# rfid.net
KiCad netlist of a schematic drawn in EAGLE
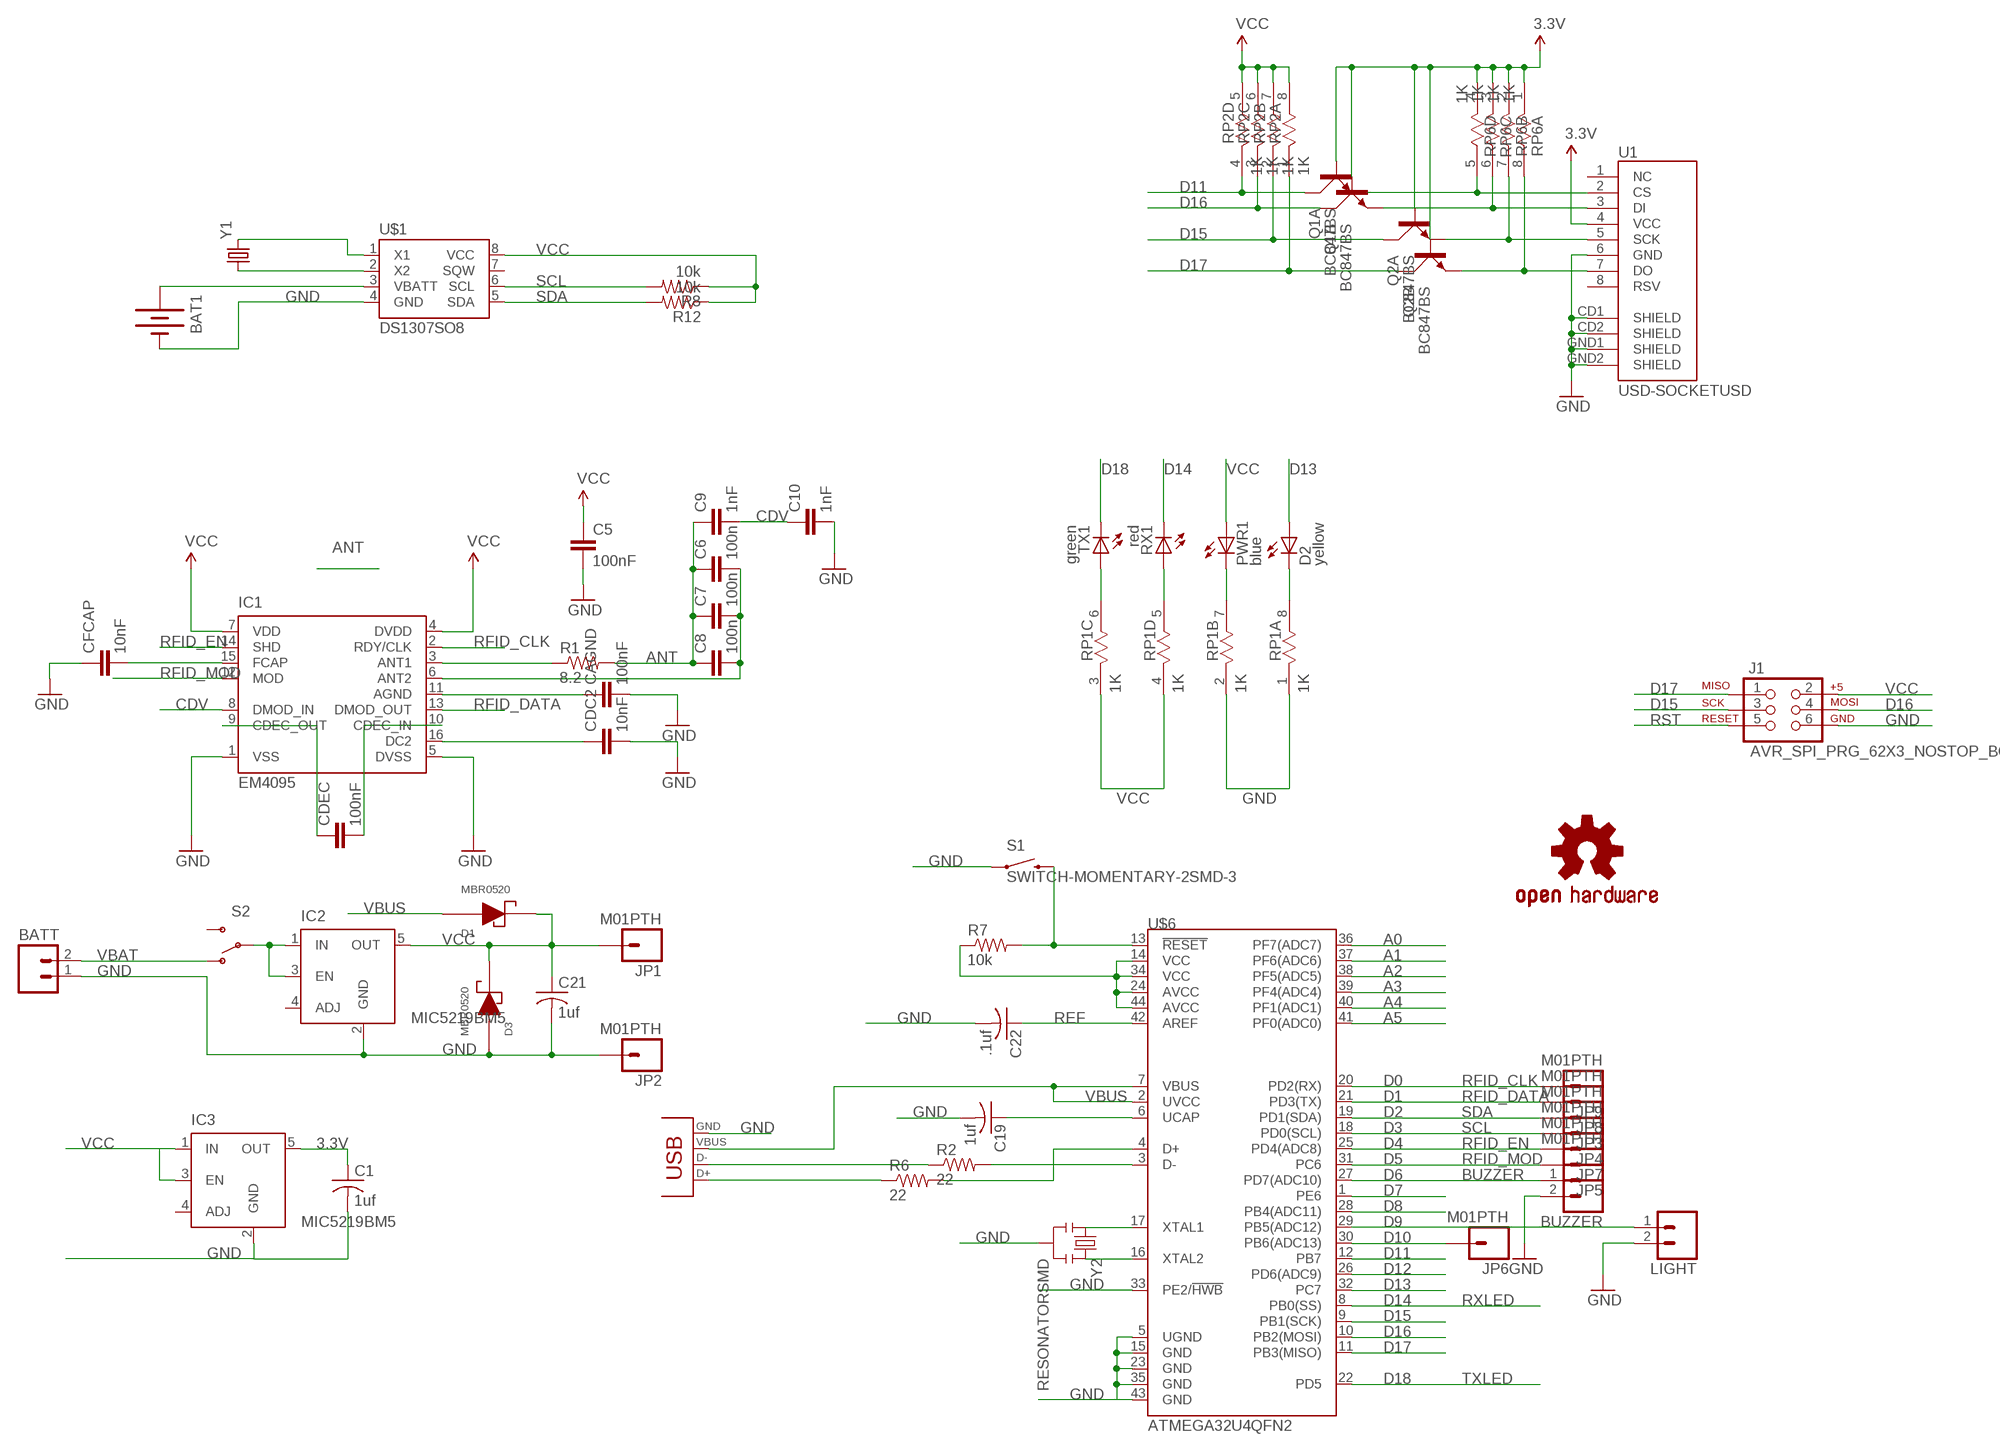
[diagram p0: schematic, sheet 1]

(export (version "E")
  (design (tool "Eeschema 10.0.6"))
  (components
    (comp (ref "BAT1")
      (value "BATTERY12MM")
      (footprint "eagle-import:BATTCON_12MM")
      (libsource (lib "eagle-import") (part "BATTERY12MM"))
    )
    (comp (ref "BATT")
      (value "M02PTH")
      (footprint "eagle-import:1X02")
      (libsource (lib "eagle-import") (part "M02PTH"))
    )
    (comp (ref "BUZZER")
      (value "M02PTH")
      (footprint "eagle-import:1X02")
      (libsource (lib "eagle-import") (part "M02PTH"))
    )
    (comp (ref "C1")
      (value "1uf")
      (footprint "eagle-import:C0603")
      (libsource (lib "eagle-import") (part "C-USC0603"))
    )
    (comp (ref "C5")
      (value "100nF")
      (footprint "eagle-import:0805")
      (libsource (lib "eagle-import") (part "CAP0805"))
    )
    (comp (ref "C6")
      (value "100n")
      (footprint "eagle-import:0805")
      (libsource (lib "eagle-import") (part "CAP0805"))
    )
    (comp (ref "C7")
      (value "100n")
      (footprint "eagle-import:0805")
      (libsource (lib "eagle-import") (part "CAP0805"))
    )
    (comp (ref "C8")
      (value "100n")
      (footprint "eagle-import:0805")
      (libsource (lib "eagle-import") (part "CAP0805"))
    )
    (comp (ref "C9")
      (value "1nF")
      (footprint "eagle-import:0805")
      (libsource (lib "eagle-import") (part "CAP0805"))
    )
    (comp (ref "C10")
      (value "1nF")
      (footprint "eagle-import:0805")
      (libsource (lib "eagle-import") (part "CAP0805"))
    )
    (comp (ref "C19")
      (value "1uf")
      (footprint "eagle-import:C0603")
      (libsource (lib "eagle-import") (part "C-USC0603"))
    )
    (comp (ref "C21")
      (value "1uf")
      (footprint "eagle-import:C0603")
      (libsource (lib "eagle-import") (part "C-USC0603"))
    )
    (comp (ref "C22")
      (value ".1uf")
      (footprint "eagle-import:C0603")
      (libsource (lib "eagle-import") (part "C-USC0603"))
    )
    (comp (ref "CAGND")
      (value "100nF")
      (footprint "eagle-import:0805")
      (libsource (lib "eagle-import") (part "CAP0805"))
    )
    (comp (ref "CDC2")
      (value "10nF")
      (footprint "eagle-import:0805")
      (libsource (lib "eagle-import") (part "CAP0805"))
    )
    (comp (ref "CDEC")
      (value "100nF")
      (footprint "eagle-import:0805")
      (libsource (lib "eagle-import") (part "CAP0805"))
    )
    (comp (ref "CFCAP")
      (value "10nF")
      (footprint "eagle-import:0805")
      (libsource (lib "eagle-import") (part "CAP0805"))
    )
    (comp (ref "D1")
      (value "MBR0520")
      (footprint "eagle-import:SOD-123")
      (libsource (lib "eagle-import") (part "MBR0520"))
    )
    (comp (ref "D2")
      (value "yellow")
      (footprint "eagle-import:LED3MM")
      (libsource (lib "eagle-import") (part "LED3MM"))
    )
    (comp (ref "D3")
      (value "MBR0520")
      (footprint "eagle-import:SOD-123")
      (libsource (lib "eagle-import") (part "MBR0520"))
    )
    (comp (ref "IC1")
      (value "EM4095")
      (footprint "eagle-import:SO16")
      (libsource (lib "eagle-import") (part "EM4095"))
    )
    (comp (ref "IC2")
      (value "MIC5219BM5")
      (footprint "eagle-import:SOT23-5")
      (fields (field (name "MF") "ALTERA CORPORATION") (field (name "MPN") "MIC5219BM5 TR"))
      (libsource (lib "eagle-import") (part "MIC5219BM5"))
    )
    (comp (ref "IC3")
      (value "MIC5219BM5")
      (footprint "eagle-import:SOT23-5")
      (fields
        (field (name "MF") "ALTERA CORPORATION")
        (field (name "MPN") "MIC5219BM5 TR")
        (field (name "MF_1") "ALTERA CORPORATION")
        (field (name "MPN_1") "MIC5219BM5 TR")
        (field (name "OC_FARNELL") "1100656")
        (field (name "OC_NEWARK") "09J8939")
      )
      (libsource (lib "eagle-import") (part "MIC5219BM5"))
    )
    (comp (ref "J1")
      (value "AVR_SPI_PRG_62X3_NOSTOP_BOT")
      (footprint "eagle-import:2X3_STOP_BOT")
      (libsource (lib "eagle-import") (part "AVR_SPI_PRG_62X3_NOSTOP_BOT"))
    )
    (comp (ref "JP1")
      (value "M01PTH")
      (footprint "eagle-import:1X01")
      (libsource (lib "eagle-import") (part "M01PTH"))
    )
    (comp (ref "JP2")
      (value "M01PTH")
      (footprint "eagle-import:1X01")
      (libsource (lib "eagle-import") (part "M01PTH"))
    )
    (comp (ref "JP3")
      (value "M01PTH")
      (footprint "eagle-import:1X01")
      (libsource (lib "eagle-import") (part "M01PTH"))
    )
    (comp (ref "JP4")
      (value "M01PTH")
      (footprint "eagle-import:1X01")
      (libsource (lib "eagle-import") (part "M01PTH"))
    )
    (comp (ref "JP5")
      (value "M01PTH")
      (footprint "eagle-import:1X01")
      (libsource (lib "eagle-import") (part "M01PTH"))
    )
    (comp (ref "JP6")
      (value "M01PTH")
      (footprint "eagle-import:1X01")
      (libsource (lib "eagle-import") (part "M01PTH"))
    )
    (comp (ref "JP7")
      (value "M01PTH")
      (footprint "eagle-import:1X01")
      (libsource (lib "eagle-import") (part "M01PTH"))
    )
    (comp (ref "JP8")
      (value "M01PTH")
      (footprint "eagle-import:1X01")
      (libsource (lib "eagle-import") (part "M01PTH"))
    )
    (comp (ref "JP9")
      (value "M01PTH")
      (footprint "eagle-import:1X01")
      (libsource (lib "eagle-import") (part "M01PTH"))
    )
    (comp (ref "LIGHT")
      (value "M02PTH")
      (footprint "eagle-import:1X02")
      (libsource (lib "eagle-import") (part "M02PTH"))
    )
    (comp (ref "PWR1")
      (value "blue")
      (footprint "eagle-import:LED3MM")
      (libsource (lib "eagle-import") (part "LED3MM"))
    )
    (comp (ref "Q1")
      (value "BC847BS")
      (footprint "eagle-import:SOT363_PHILIPS")
      (libsource (lib "eagle-import") (part "BC847BS"))
    )
    (comp (ref "Q2")
      (value "BC847BS")
      (footprint "eagle-import:SOT363_PHILIPS")
      (libsource (lib "eagle-import") (part "BC847BS"))
    )
    (comp (ref "R1")
      (value "8.2")
      (footprint "eagle-import:0805")
      (libsource (lib "eagle-import") (part "SparkFun-Passives_RESISTOR0805-RES"))
    )
    (comp (ref "R2")
      (value "22")
      (footprint "eagle-import:0603-RES")
      (libsource (lib "eagle-import") (part "RESISTOR0603-RES"))
    )
    (comp (ref "R6")
      (value "22")
      (footprint "eagle-import:0603-RES")
      (libsource (lib "eagle-import") (part "RESISTOR0603-RES"))
    )
    (comp (ref "R7")
      (value "10k")
      (footprint "eagle-import:0603-RES")
      (libsource (lib "eagle-import") (part "RESISTOR0603-RES"))
    )
    (comp (ref "R8")
      (value "10k")
      (footprint "eagle-import:0603-RES")
      (libsource (lib "eagle-import") (part "RESISTOR0603-RES"))
    )
    (comp (ref "R12")
      (value "10k")
      (footprint "eagle-import:0603-RES")
      (libsource (lib "eagle-import") (part "RESISTOR0603-RES"))
    )
    (comp (ref "RP1")
      (value "1K")
      (footprint "eagle-import:RES4NT")
      (libsource (lib "eagle-import") (part "RES4NT"))
    )
    (comp (ref "RP2")
      (value "1K")
      (footprint "eagle-import:RES4NT")
      (libsource (lib "eagle-import") (part "RES4NT"))
    )
    (comp (ref "RP6")
      (value "1K")
      (footprint "eagle-import:RES4NT")
      (libsource (lib "eagle-import") (part "RES4NT"))
    )
    (comp (ref "RX1")
      (value "red")
      (footprint "eagle-import:LED3MM")
      (libsource (lib "eagle-import") (part "LED3MM"))
    )
    (comp (ref "S1")
      (value "SWITCH-MOMENTARY-2SMD-3")
      (footprint "eagle-import:TACTILE_SWITCH_SMD-3")
      (libsource (lib "eagle-import") (part "SWITCH-MOMENTARY-2SMD-3"))
    )
    (comp (ref "S2")
      (value "SWITCH-SPDT-SMD-A")
      (footprint "eagle-import:SWITCH-SPST-SMD-A")
      (libsource (lib "eagle-import") (part "SWITCH-SPDT-SMD-A"))
    )
    (comp (ref "TX1")
      (value "green")
      (footprint "eagle-import:LED3MM")
      (libsource (lib "eagle-import") (part "LED3MM"))
    )
    (comp (ref "U$1")
      (value "DS1307SO8")
      (footprint "eagle-import:SO08")
      (libsource (lib "eagle-import") (part "DS1307SO8"))
    )
    (comp (ref "U$2")
      (value "USB_MICROB")
      (footprint "eagle-import:USB-MICROB")
      (libsource (lib "eagle-import") (part "USB_MICROB"))
    )
    (comp (ref "U$3")
      (value "OSHW-LOGOL")
      (footprint "eagle-import:OSHW-LOGO-L")
      (libsource (lib "eagle-import") (part "OSHW-LOGOL"))
    )
    (comp (ref "U$6")
      (value "ATMEGA32U4QFN2")
      (footprint "eagle-import:QFN-44-NOPAD")
      (libsource (lib "eagle-import") (part "ATMEGA32U4QFN2"))
    )
    (comp (ref "U1")
      (value "USD-SOCKETUSD")
      (footprint "eagle-import:USD-SOCKET-PP")
      (libsource (lib "eagle-import") (part "USD-SOCKETUSD"))
    )
    (comp (ref "Y1")
      (value "CRYSTAL5X2")
      (footprint "eagle-import:CRYSTAL-SMD-5X2")
      (libsource (lib "eagle-import") (part "CRYSTAL5X2"))
    )
    (comp (ref "Y2")
      (value "RESONATORSMD")
      (footprint "eagle-import:RESONATOR-SMD")
      (libsource (lib "eagle-import") (part "RESONATORSMD"))
    )
  )
  (nets
    (net (code "1") (name "/A0") (class "Default")
      (node (ref "U$6") (pin "36") (pinfunction "PF7(ADC7)_36") (pintype "bidirectional"))
    )
    (net (code "2") (name "/A1") (class "Default")
      (node (ref "U$6") (pin "37") (pinfunction "PF6(ADC6)_37") (pintype "bidirectional"))
    )
    (net (code "3") (name "/A2") (class "Default")
      (node (ref "U$6") (pin "38") (pinfunction "PF5(ADC5)_38") (pintype "bidirectional"))
    )
    (net (code "4") (name "/A3") (class "Default")
      (node (ref "U$6") (pin "39") (pinfunction "PF4(ADC4)_39") (pintype "bidirectional"))
    )
    (net (code "5") (name "/A4") (class "Default")
      (node (ref "U$6") (pin "40") (pinfunction "PF1(ADC1)_40") (pintype "bidirectional"))
    )
    (net (code "6") (name "/A5") (class "Default")
      (node (ref "U$6") (pin "41") (pinfunction "PF0(ADC0)_41") (pintype "bidirectional"))
    )
    (net (code "7") (name "/ANT") (class "Default")
      (node (ref "C6") (pin "1") (pinfunction "1_1") (pintype "passive"))
      (node (ref "C7") (pin "1") (pinfunction "1_1") (pintype "passive"))
      (node (ref "C8") (pin "1") (pinfunction "1_1") (pintype "passive"))
      (node (ref "C9") (pin "1") (pinfunction "1_1") (pintype "passive"))
      (node (ref "R1") (pin "2") (pinfunction "2_2") (pintype "passive"))
    )
    (net (code "8") (name "/CDV") (class "Default")
      (node (ref "C10") (pin "1") (pinfunction "1_1") (pintype "passive"))
      (node (ref "C9") (pin "2") (pinfunction "2_2") (pintype "passive"))
      (node (ref "IC1") (pin "8") (pinfunction "DMOD_IN_8") (pintype "input"))
    )
    (net (code "9") (name "/D6") (class "Default")
      (node (ref "BUZZER") (pin "1") (pinfunction "1_1") (pintype "passive"))
      (node (ref "U$6") (pin "27") (pinfunction "PD7(ADC10)_27") (pintype "bidirectional"))
    )
    (net (code "10") (name "/D7") (class "Default")
      (node (ref "U$6") (pin "1") (pinfunction "PE6_1") (pintype "bidirectional"))
    )
    (net (code "11") (name "/D8") (class "Default")
      (node (ref "U$6") (pin "28") (pinfunction "PB4(ADC11)_28") (pintype "bidirectional"))
    )
    (net (code "12") (name "/D9") (class "Default")
      (node (ref "LIGHT") (pin "1") (pinfunction "1_1") (pintype "passive"))
      (node (ref "U$6") (pin "29") (pinfunction "PB5(ADC12)_29") (pintype "bidirectional"))
    )
    (net (code "13") (name "/D10") (class "Default")
      (node (ref "JP6") (pin "1") (pinfunction "1_1") (pintype "passive"))
      (node (ref "U$6") (pin "30") (pinfunction "PB6(ADC13)_30") (pintype "bidirectional"))
    )
    (net (code "14") (name "/D11") (class "Default")
      (node (ref "Q1") (pin "6") (pinfunction "C_6") (pintype "passive"))
      (node (ref "RP2") (pin "4") (pinfunction "1_4") (pintype "passive"))
      (node (ref "U$6") (pin "12") (pinfunction "PB7_12") (pintype "bidirectional"))
    )
    (net (code "15") (name "/D12") (class "Default")
      (node (ref "U$6") (pin "26") (pinfunction "PD6(ADC9)_26") (pintype "bidirectional"))
    )
    (net (code "16") (name "/D13") (class "Default")
      (node (ref "D2") (pin "A") (pinfunction "A_A") (pintype "passive"))
      (node (ref "U$6") (pin "32") (pinfunction "PC7_32") (pintype "bidirectional"))
    )
    (net (code "17") (name "/D14") (class "Default")
      (node (ref "RX1") (pin "K") (pinfunction "C_K") (pintype "passive"))
      (node (ref "U$6") (pin "8") (pinfunction "PB0(SS)_8") (pintype "bidirectional"))
    )
    (net (code "18") (name "/D15") (class "Default")
      (node (ref "J1") (pin "3") (pinfunction "3_3") (pintype "passive"))
      (node (ref "Q2") (pin "6") (pinfunction "C_6") (pintype "passive"))
      (node (ref "RP2") (pin "2") (pinfunction "1_2") (pintype "passive"))
      (node (ref "U$6") (pin "9") (pinfunction "PB1(SCK)_9") (pintype "bidirectional"))
    )
    (net (code "19") (name "/D16") (class "Default")
      (node (ref "J1") (pin "4") (pinfunction "4_4") (pintype "passive"))
      (node (ref "Q1") (pin "3") (pinfunction "C_3") (pintype "passive"))
      (node (ref "RP2") (pin "3") (pinfunction "1_3") (pintype "passive"))
      (node (ref "U$6") (pin "10") (pinfunction "PB2(MOSI)_10") (pintype "bidirectional"))
    )
    (net (code "20") (name "/D17") (class "Default")
      (node (ref "J1") (pin "1") (pinfunction "1_1") (pintype "passive"))
      (node (ref "Q2") (pin "3") (pinfunction "C_3") (pintype "passive"))
      (node (ref "RP2") (pin "1") (pinfunction "1_1") (pintype "passive"))
      (node (ref "U$6") (pin "11") (pinfunction "PB3(MISO)_11") (pintype "bidirectional"))
    )
    (net (code "21") (name "/D18") (class "Default")
      (node (ref "TX1") (pin "K") (pinfunction "C_K") (pintype "passive"))
      (node (ref "U$6") (pin "22") (pinfunction "PD5_22") (pintype "bidirectional"))
    )
    (net (code "22") (name "/REF") (class "Default")
      (node (ref "C22") (pin "1") (pinfunction "1_1") (pintype "passive"))
      (node (ref "U$6") (pin "42") (pinfunction "AREF_42") (pintype "bidirectional"))
    )
    (net (code "23") (name "/RFID_CLK") (class "Default")
      (node (ref "IC1") (pin "2") (pinfunction "RDY/CLK_2") (pintype "output"))
      (node (ref "JP9") (pin "1") (pinfunction "1_1") (pintype "passive"))
      (node (ref "U$6") (pin "20") (pinfunction "PD2(RX)_20") (pintype "bidirectional"))
    )
    (net (code "24") (name "/RFID_DATA") (class "Default")
      (node (ref "IC1") (pin "13") (pinfunction "DMOD_OUT_13") (pintype "output"))
      (node (ref "JP8") (pin "1") (pinfunction "1_1") (pintype "passive"))
      (node (ref "U$6") (pin "21") (pinfunction "PD3(TX)_21") (pintype "bidirectional"))
    )
    (net (code "25") (name "/RFID_EN") (class "Default")
      (node (ref "IC1") (pin "14") (pinfunction "SHD_14") (pintype "input"))
      (node (ref "JP7") (pin "1") (pinfunction "1_1") (pintype "passive"))
      (node (ref "U$6") (pin "25") (pinfunction "PD4(ADC8)_25") (pintype "bidirectional"))
    )
    (net (code "26") (name "/RFID_MOD") (class "Default")
      (node (ref "IC1") (pin "12") (pinfunction "MOD_12") (pintype "input"))
      (node (ref "JP5") (pin "1") (pinfunction "1_1") (pintype "passive"))
      (node (ref "U$6") (pin "31") (pinfunction "PC6_31") (pintype "bidirectional"))
    )
    (net (code "27") (name "/RST") (class "Default")
      (node (ref "J1") (pin "5") (pinfunction "5_5") (pintype "passive"))
      (node (ref "R7") (pin "2") (pinfunction "2_2") (pintype "passive"))
      (node (ref "S1") (pin "P$2") (pinfunction "2_P$2") (pintype "passive"))
      (node (ref "U$6") (pin "13") (pinfunction "~{RESET}_13") (pintype "bidirectional"))
    )
    (net (code "28") (name "/SCL") (class "Default")
      (node (ref "JP4") (pin "1") (pinfunction "1_1") (pintype "passive"))
      (node (ref "R8") (pin "2") (pinfunction "2_2") (pintype "passive"))
      (node (ref "U$1") (pin "6") (pinfunction "SCL_6") (pintype "bidirectional"))
      (node (ref "U$6") (pin "18") (pinfunction "PD0(SCL)_18") (pintype "bidirectional"))
    )
    (net (code "29") (name "/SDA") (class "Default")
      (node (ref "JP3") (pin "1") (pinfunction "1_1") (pintype "passive"))
      (node (ref "R12") (pin "2") (pinfunction "2_2") (pintype "passive"))
      (node (ref "U$1") (pin "5") (pinfunction "SDA_5") (pintype "bidirectional"))
      (node (ref "U$6") (pin "19") (pinfunction "PD1(SDA)_19") (pintype "bidirectional"))
    )
    (net (code "30") (name "/VBAT") (class "Default")
      (node (ref "BATT") (pin "2") (pinfunction "2_2") (pintype "passive"))
      (node (ref "S2") (pin "1") (pinfunction "O_1") (pintype "passive"))
    )
    (net (code "31") (name "/VBUS") (class "Default")
      (node (ref "D1") (pin "2") (pinfunction "AN_2") (pintype "passive"))
      (node (ref "U$2") (pin "P1") (pinfunction "P$2_P1") (pintype "bidirectional"))
      (node (ref "U$6") (pin "2") (pinfunction "UVCC_2") (pintype "bidirectional"))
      (node (ref "U$6") (pin "7") (pinfunction "VBUS_7") (pintype "bidirectional"))
    )
    (net (code "32") (name "3.3V") (class "Default")
      (node (ref "C1") (pin "1") (pinfunction "1_1") (pintype "passive"))
      (node (ref "IC3") (pin "5") (pinfunction "OUT_5") (pintype "output"))
      (node (ref "Q1") (pin "2") (pinfunction "B_2") (pintype "passive"))
      (node (ref "Q1") (pin "5") (pinfunction "B_5") (pintype "passive"))
      (node (ref "Q2") (pin "2") (pinfunction "B_2") (pintype "passive"))
      (node (ref "Q2") (pin "5") (pinfunction "B_5") (pintype "passive"))
      (node (ref "RP6") (pin "1") (pinfunction "1_1") (pintype "passive"))
      (node (ref "RP6") (pin "2") (pinfunction "1_2") (pintype "passive"))
      (node (ref "RP6") (pin "3") (pinfunction "1_3") (pintype "passive"))
      (node (ref "RP6") (pin "4") (pinfunction "1_4") (pintype "passive"))
      (node (ref "U1") (pin "4") (pinfunction "VCC_4") (pintype "bidirectional"))
    )
    (net (code "33") (name "GND") (class "Default")
      (node (ref "BAT1") (pin "GND") (pinfunction "-_GND") (pintype "power_in"))
      (node (ref "BATT") (pin "1") (pinfunction "1_1") (pintype "passive"))
      (node (ref "BUZZER") (pin "2") (pinfunction "2_2") (pintype "passive"))
      (node (ref "C1") (pin "2") (pinfunction "2_2") (pintype "passive"))
      (node (ref "C10") (pin "2") (pinfunction "2_2") (pintype "passive"))
      (node (ref "C19") (pin "2") (pinfunction "2_2") (pintype "passive"))
      (node (ref "C21") (pin "2") (pinfunction "2_2") (pintype "passive"))
      (node (ref "C22") (pin "2") (pinfunction "2_2") (pintype "passive"))
      (node (ref "C5") (pin "2") (pinfunction "2_2") (pintype "passive"))
      (node (ref "CAGND") (pin "2") (pinfunction "2_2") (pintype "passive"))
      (node (ref "CDC2") (pin "2") (pinfunction "2_2") (pintype "passive"))
      (node (ref "CFCAP") (pin "1") (pinfunction "1_1") (pintype "passive"))
      (node (ref "D3") (pin "2") (pinfunction "AN_2") (pintype "passive"))
      (node (ref "IC1") (pin "1") (pinfunction "VSS_1") (pintype "power_in"))
      (node (ref "IC1") (pin "5") (pinfunction "DVSS_5") (pintype "power_in"))
      (node (ref "IC2") (pin "2") (pinfunction "GND_2") (pintype "power_in"))
      (node (ref "IC3") (pin "2") (pinfunction "GND_2") (pintype "power_in"))
      (node (ref "J1") (pin "6") (pinfunction "6_6") (pintype "passive"))
      (node (ref "JP2") (pin "1") (pinfunction "1_1") (pintype "passive"))
      (node (ref "LIGHT") (pin "2") (pinfunction "2_2") (pintype "passive"))
      (node (ref "RP1") (pin "1") (pinfunction "1_1") (pintype "passive"))
      (node (ref "RP1") (pin "2") (pinfunction "1_2") (pintype "passive"))
      (node (ref "S1") (pin "P$1") (pinfunction "1_P$1") (pintype "passive"))
      (node (ref "U$1") (pin "4") (pinfunction "GND_4") (pintype "bidirectional"))
      (node (ref "U$2") (pin "P$1") (pinfunction "P$1_P$1") (pintype "bidirectional"))
      (node (ref "U$2") (pin "P$2") (pinfunction "P$1_P$2") (pintype "bidirectional"))
      (node (ref "U$2") (pin "P$3") (pinfunction "P$1_P$3") (pintype "bidirectional"))
      (node (ref "U$2") (pin "P$4") (pinfunction "P$1_P$4") (pintype "bidirectional"))
      (node (ref "U$2") (pin "P$5") (pinfunction "P$1_P$5") (pintype "bidirectional"))
      (node (ref "U$2") (pin "P$6") (pinfunction "P$1_P$6") (pintype "bidirectional"))
      (node (ref "U$2") (pin "P4") (pinfunction "P$1_P4") (pintype "bidirectional"))
      (node (ref "U$2") (pin "P5") (pinfunction "P$1_P5") (pintype "bidirectional"))
      (node (ref "U$6") (pin "15") (pinfunction "GND_15") (pintype "bidirectional"))
      (node (ref "U$6") (pin "23") (pinfunction "GND_23") (pintype "bidirectional"))
      (node (ref "U$6") (pin "33") (pinfunction "PE2/~{HWB}_33") (pintype "bidirectional"))
      (node (ref "U$6") (pin "35") (pinfunction "GND_35") (pintype "bidirectional"))
      (node (ref "U$6") (pin "43") (pinfunction "GND_43") (pintype "bidirectional"))
      (node (ref "U$6") (pin "5") (pinfunction "UGND_5") (pintype "bidirectional"))
      (node (ref "U1") (pin "6") (pinfunction "GND_6") (pintype "bidirectional"))
      (node (ref "U1") (pin "CD1") (pinfunction "SHIELD_CD1") (pintype "bidirectional"))
      (node (ref "U1") (pin "CD2") (pinfunction "SHIELD_CD2") (pintype "bidirectional"))
      (node (ref "U1") (pin "GND1") (pinfunction "SHIELD_GND1") (pintype "bidirectional"))
      (node (ref "U1") (pin "GND2") (pinfunction "SHIELD_GND2") (pintype "bidirectional"))
      (node (ref "Y2") (pin "2") (pinfunction "2_2") (pintype "passive"))
    )
    (net (code "34") (name "Net-(BAT1-+)") (class "Default")
      (node (ref "BAT1") (pin "PWR@1") (pinfunction "+_PWR@1") (pintype "power_in"))
      (node (ref "U$1") (pin "3") (pinfunction "VBATT_3") (pintype "bidirectional"))
    )
    (net (code "35") (name "Net-(D2-C)") (class "Default")
      (node (ref "D2") (pin "K") (pinfunction "C_K") (pintype "passive"))
      (node (ref "RP1") (pin "8") (pinfunction "2_8") (pintype "passive"))
    )
    (net (code "36") (name "Net-(IC1-AGND)") (class "Default")
      (node (ref "CAGND") (pin "1") (pinfunction "1_1") (pintype "passive"))
      (node (ref "IC1") (pin "11") (pinfunction "AGND_11") (pintype "power_in"))
    )
    (net (code "37") (name "Net-(IC1-ANT1)") (class "Default")
      (node (ref "IC1") (pin "3") (pinfunction "ANT1_3") (pintype "passive"))
      (node (ref "R1") (pin "1") (pinfunction "1_1") (pintype "passive"))
    )
    (net (code "38") (name "Net-(IC1-ANT2)") (class "Default")
      (node (ref "C6") (pin "2") (pinfunction "2_2") (pintype "passive"))
      (node (ref "C7") (pin "2") (pinfunction "2_2") (pintype "passive"))
      (node (ref "C8") (pin "2") (pinfunction "2_2") (pintype "passive"))
      (node (ref "IC1") (pin "6") (pinfunction "ANT2_6") (pintype "passive"))
    )
    (net (code "39") (name "Net-(IC1-CDEC_IN)") (class "Default")
      (node (ref "CDEC") (pin "2") (pinfunction "2_2") (pintype "passive"))
      (node (ref "IC1") (pin "10") (pinfunction "CDEC_IN_10") (pintype "input"))
    )
    (net (code "40") (name "Net-(IC1-CDEC_OUT)") (class "Default")
      (node (ref "CDEC") (pin "1") (pinfunction "1_1") (pintype "passive"))
      (node (ref "IC1") (pin "9") (pinfunction "CDEC_OUT_9") (pintype "output"))
    )
    (net (code "41") (name "Net-(IC1-DC2)") (class "Default")
      (node (ref "CDC2") (pin "1") (pinfunction "1_1") (pintype "passive"))
      (node (ref "IC1") (pin "16") (pinfunction "DC2_16") (pintype "passive"))
    )
    (net (code "42") (name "Net-(IC1-FCAP)") (class "Default")
      (node (ref "CFCAP") (pin "2") (pinfunction "2_2") (pintype "passive"))
      (node (ref "IC1") (pin "15") (pinfunction "FCAP_15") (pintype "passive"))
    )
    (net (code "43") (name "Net-(IC2-EN)") (class "Default")
      (node (ref "IC2") (pin "1") (pinfunction "IN_1") (pintype "input"))
      (node (ref "IC2") (pin "3") (pinfunction "EN_3") (pintype "input"))
      (node (ref "S2") (pin "2") (pinfunction "P_2") (pintype "passive"))
    )
    (net (code "44") (name "Net-(PWR1-C)") (class "Default")
      (node (ref "PWR1") (pin "K") (pinfunction "C_K") (pintype "passive"))
      (node (ref "RP1") (pin "7") (pinfunction "2_7") (pintype "passive"))
    )
    (net (code "45") (name "Net-(Q1A-E)") (class "Default")
      (node (ref "Q1") (pin "1") (pinfunction "E_1") (pintype "passive"))
      (node (ref "RP6") (pin "5") (pinfunction "2_5") (pintype "passive"))
      (node (ref "U1") (pin "2") (pinfunction "CS_2") (pintype "bidirectional"))
    )
    (net (code "46") (name "Net-(Q1B-E)") (class "Default")
      (node (ref "Q1") (pin "4") (pinfunction "E_4") (pintype "passive"))
      (node (ref "RP6") (pin "6") (pinfunction "2_6") (pintype "passive"))
      (node (ref "U1") (pin "3") (pinfunction "DI_3") (pintype "bidirectional"))
    )
    (net (code "47") (name "Net-(Q2A-E)") (class "Default")
      (node (ref "Q2") (pin "1") (pinfunction "E_1") (pintype "passive"))
      (node (ref "RP6") (pin "7") (pinfunction "2_7") (pintype "passive"))
      (node (ref "U1") (pin "5") (pinfunction "SCK_5") (pintype "bidirectional"))
    )
    (net (code "48") (name "Net-(Q2B-E)") (class "Default")
      (node (ref "Q2") (pin "4") (pinfunction "E_4") (pintype "passive"))
      (node (ref "RP6") (pin "8") (pinfunction "2_8") (pintype "passive"))
      (node (ref "U1") (pin "7") (pinfunction "DO_7") (pintype "bidirectional"))
    )
    (net (code "49") (name "Net-(RP1C-2)") (class "Default")
      (node (ref "RP1") (pin "6") (pinfunction "2_6") (pintype "passive"))
      (node (ref "TX1") (pin "A") (pinfunction "A_A") (pintype "passive"))
    )
    (net (code "50") (name "Net-(RP1D-2)") (class "Default")
      (node (ref "RP1") (pin "5") (pinfunction "2_5") (pintype "passive"))
      (node (ref "RX1") (pin "A") (pinfunction "A_A") (pintype "passive"))
    )
    (net (code "51") (name "Net-(U$1-X1)") (class "Default")
      (node (ref "U$1") (pin "1") (pinfunction "X1_1") (pintype "bidirectional"))
      (node (ref "Y1") (pin "2") (pinfunction "2_2") (pintype "passive"))
    )
    (net (code "52") (name "Net-(U$1-X2)") (class "Default")
      (node (ref "U$1") (pin "2") (pinfunction "X2_2") (pintype "bidirectional"))
      (node (ref "Y1") (pin "1") (pinfunction "1_1") (pintype "passive"))
    )
    (net (code "53") (name "Net-(U$2-P$3)") (class "Default")
      (node (ref "R2") (pin "1") (pinfunction "1_1") (pintype "passive"))
      (node (ref "U$2") (pin "P2") (pinfunction "P$3_P2") (pintype "bidirectional"))
    )
    (net (code "54") (name "Net-(U$2-P$4)") (class "Default")
      (node (ref "R6") (pin "1") (pinfunction "1_1") (pintype "passive"))
      (node (ref "U$2") (pin "P3") (pinfunction "P$4_P3") (pintype "bidirectional"))
    )
    (net (code "55") (name "Net-(U$6-D+)") (class "Default")
      (node (ref "R6") (pin "2") (pinfunction "2_2") (pintype "passive"))
      (node (ref "U$6") (pin "4") (pinfunction "D+_4") (pintype "bidirectional"))
    )
    (net (code "56") (name "Net-(U$6-D-)") (class "Default")
      (node (ref "R2") (pin "2") (pinfunction "2_2") (pintype "passive"))
      (node (ref "U$6") (pin "3") (pinfunction "D-_3") (pintype "bidirectional"))
    )
    (net (code "57") (name "Net-(U$6-UCAP)") (class "Default")
      (node (ref "C19") (pin "1") (pinfunction "1_1") (pintype "passive"))
      (node (ref "U$6") (pin "6") (pinfunction "UCAP_6") (pintype "bidirectional"))
    )
    (net (code "58") (name "Net-(U$6-XTAL1)") (class "Default")
      (node (ref "U$6") (pin "17") (pinfunction "XTAL1_17") (pintype "bidirectional"))
      (node (ref "Y2") (pin "1") (pinfunction "1_1") (pintype "passive"))
    )
    (net (code "59") (name "Net-(U$6-XTAL2)") (class "Default")
      (node (ref "U$6") (pin "16") (pinfunction "XTAL2_16") (pintype "bidirectional"))
      (node (ref "Y2") (pin "3") (pinfunction "3_3") (pintype "passive"))
    )
    (net (code "60") (name "VCC") (class "Default")
      (node (ref "C21") (pin "1") (pinfunction "1_1") (pintype "passive"))
      (node (ref "C5") (pin "1") (pinfunction "1_1") (pintype "passive"))
      (node (ref "D1") (pin "1") (pinfunction "CA_1") (pintype "passive"))
      (node (ref "D3") (pin "1") (pinfunction "CA_1") (pintype "passive"))
      (node (ref "IC1") (pin "4") (pinfunction "DVDD_4") (pintype "power_in"))
      (node (ref "IC1") (pin "7") (pinfunction "VDD_7") (pintype "power_in"))
      (node (ref "IC2") (pin "5") (pinfunction "OUT_5") (pintype "output"))
      (node (ref "IC3") (pin "1") (pinfunction "IN_1") (pintype "input"))
      (node (ref "IC3") (pin "3") (pinfunction "EN_3") (pintype "input"))
      (node (ref "J1") (pin "2") (pinfunction "2_2") (pintype "passive"))
      (node (ref "JP1") (pin "1") (pinfunction "1_1") (pintype "passive"))
      (node (ref "PWR1") (pin "A") (pinfunction "A_A") (pintype "passive"))
      (node (ref "R12") (pin "1") (pinfunction "1_1") (pintype "passive"))
      (node (ref "R7") (pin "1") (pinfunction "1_1") (pintype "passive"))
      (node (ref "R8") (pin "1") (pinfunction "1_1") (pintype "passive"))
      (node (ref "RP1") (pin "3") (pinfunction "1_3") (pintype "passive"))
      (node (ref "RP1") (pin "4") (pinfunction "1_4") (pintype "passive"))
      (node (ref "RP2") (pin "5") (pinfunction "2_5") (pintype "passive"))
      (node (ref "RP2") (pin "6") (pinfunction "2_6") (pintype "passive"))
      (node (ref "RP2") (pin "7") (pinfunction "2_7") (pintype "passive"))
      (node (ref "RP2") (pin "8") (pinfunction "2_8") (pintype "passive"))
      (node (ref "U$1") (pin "8") (pinfunction "VCC_8") (pintype "bidirectional"))
      (node (ref "U$6") (pin "14") (pinfunction "VCC_14") (pintype "bidirectional"))
      (node (ref "U$6") (pin "24") (pinfunction "AVCC_24") (pintype "bidirectional"))
      (node (ref "U$6") (pin "34") (pinfunction "VCC_34") (pintype "bidirectional"))
      (node (ref "U$6") (pin "44") (pinfunction "AVCC_44") (pintype "bidirectional"))
    )
    (net (code "61") (name "unconnected-(IC2-ADJ-Pad4)") (class "Default")
      (node (ref "IC2") (pin "4") (pinfunction "ADJ_4") (pintype "passive"))
    )
    (net (code "62") (name "unconnected-(IC3-ADJ-Pad4)") (class "Default")
      (node (ref "IC3") (pin "4") (pinfunction "ADJ_4") (pintype "passive"))
    )
    (net (code "63") (name "unconnected-(S2-S-Pad3)") (class "Default")
      (node (ref "S2") (pin "3") (pinfunction "S_3") (pintype "passive"))
    )
    (net (code "64") (name "unconnected-(U$1-SQW-Pad7)") (class "Default")
      (node (ref "U$1") (pin "7") (pinfunction "SQW_7") (pintype "bidirectional"))
    )
    (net (code "65") (name "unconnected-(U1-NC-Pad1)") (class "Default")
      (node (ref "U1") (pin "1") (pinfunction "NC_1") (pintype "bidirectional"))
    )
    (net (code "66") (name "unconnected-(U1-RSV-Pad8)") (class "Default")
      (node (ref "U1") (pin "8") (pinfunction "RSV_8") (pintype "bidirectional"))
    )
  )
)
